# Main.net
KiCad netlist of a schematic drawn in EAGLE
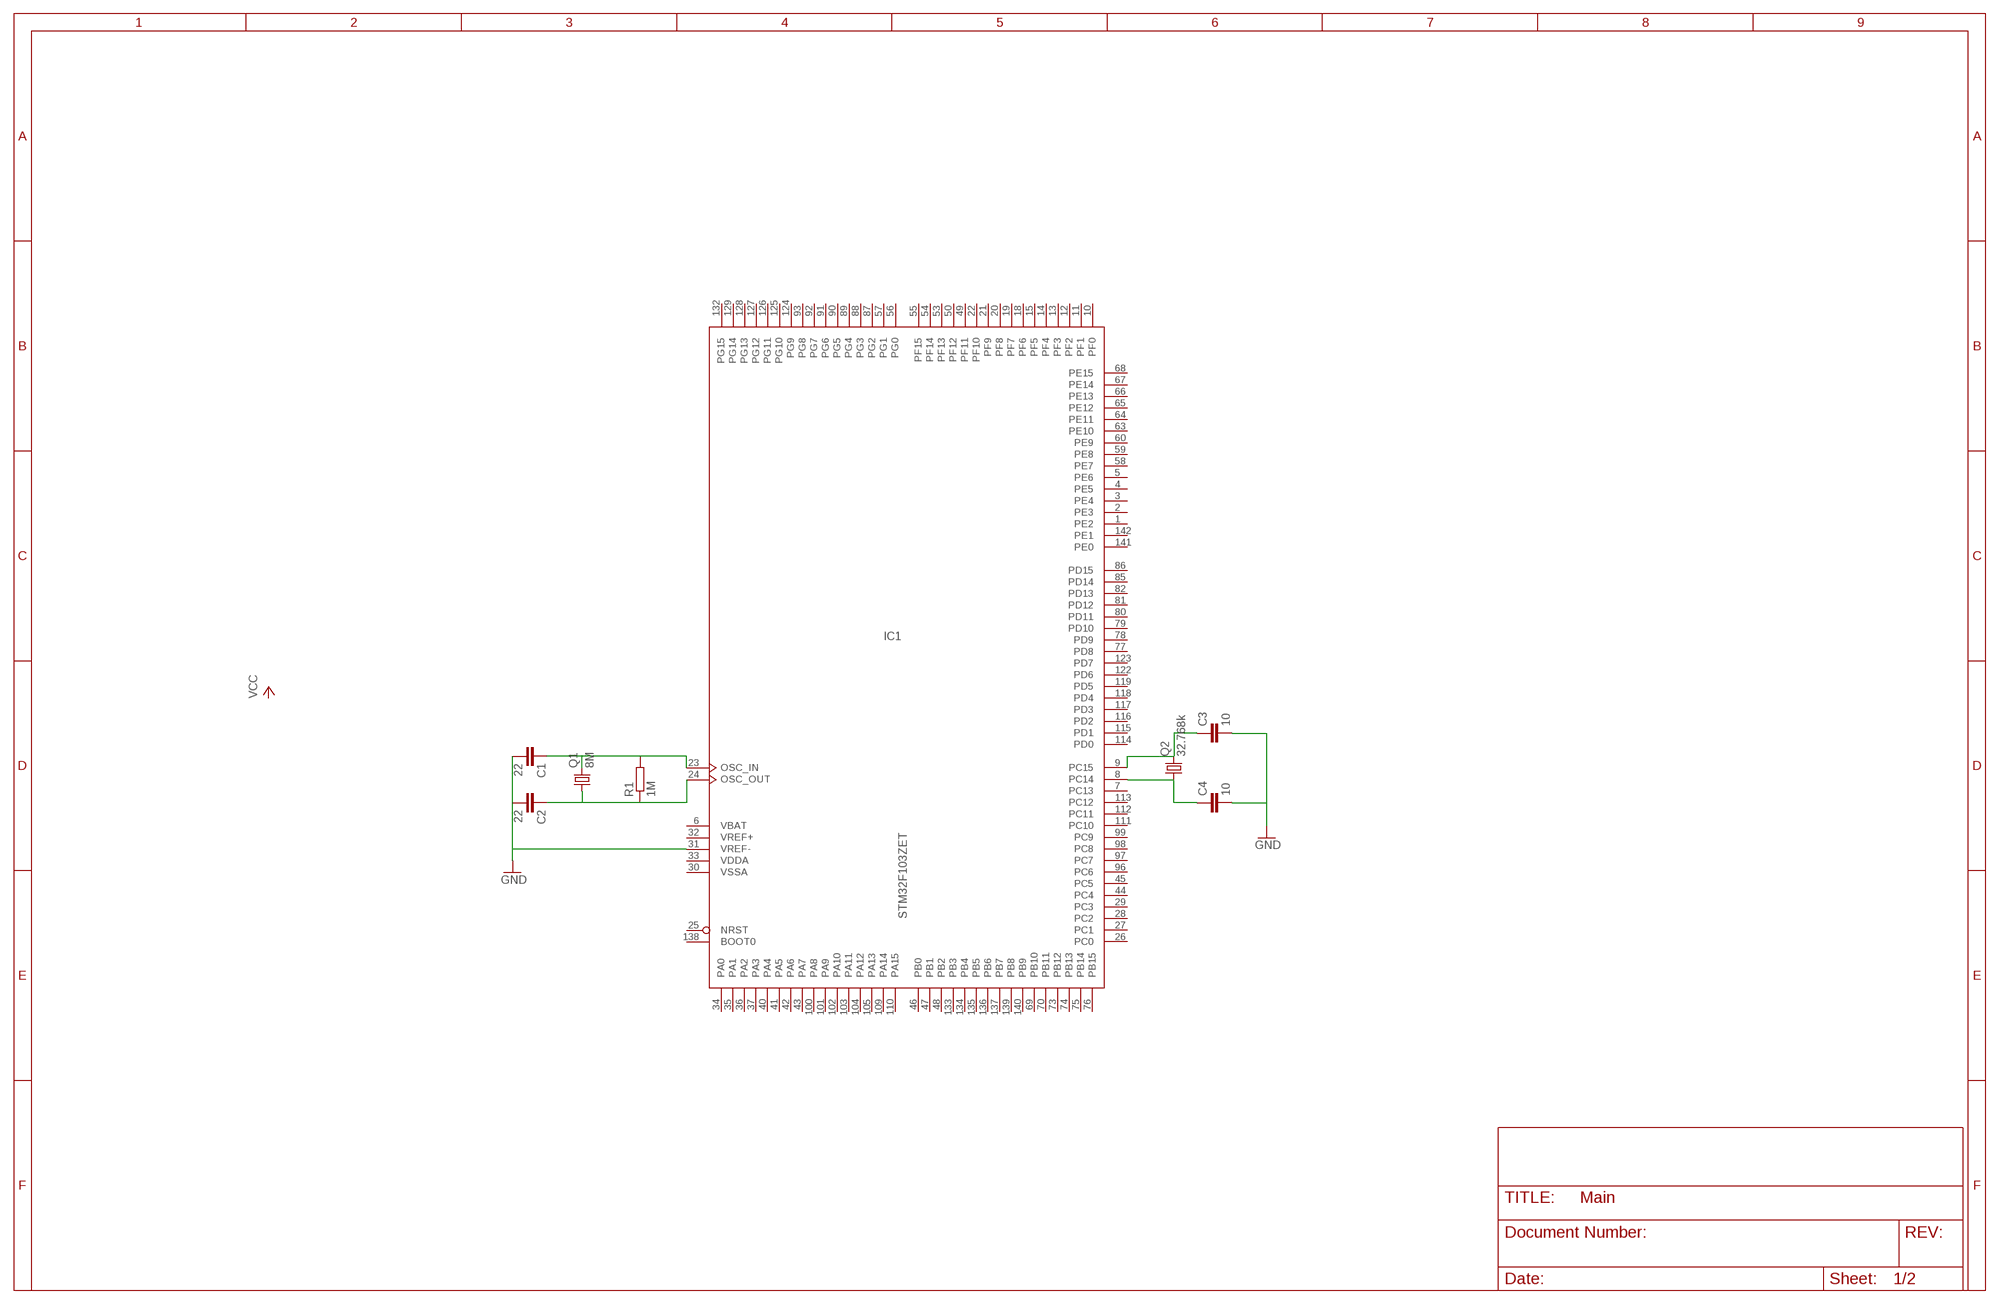
[diagram p0: schematic, sheet 1]
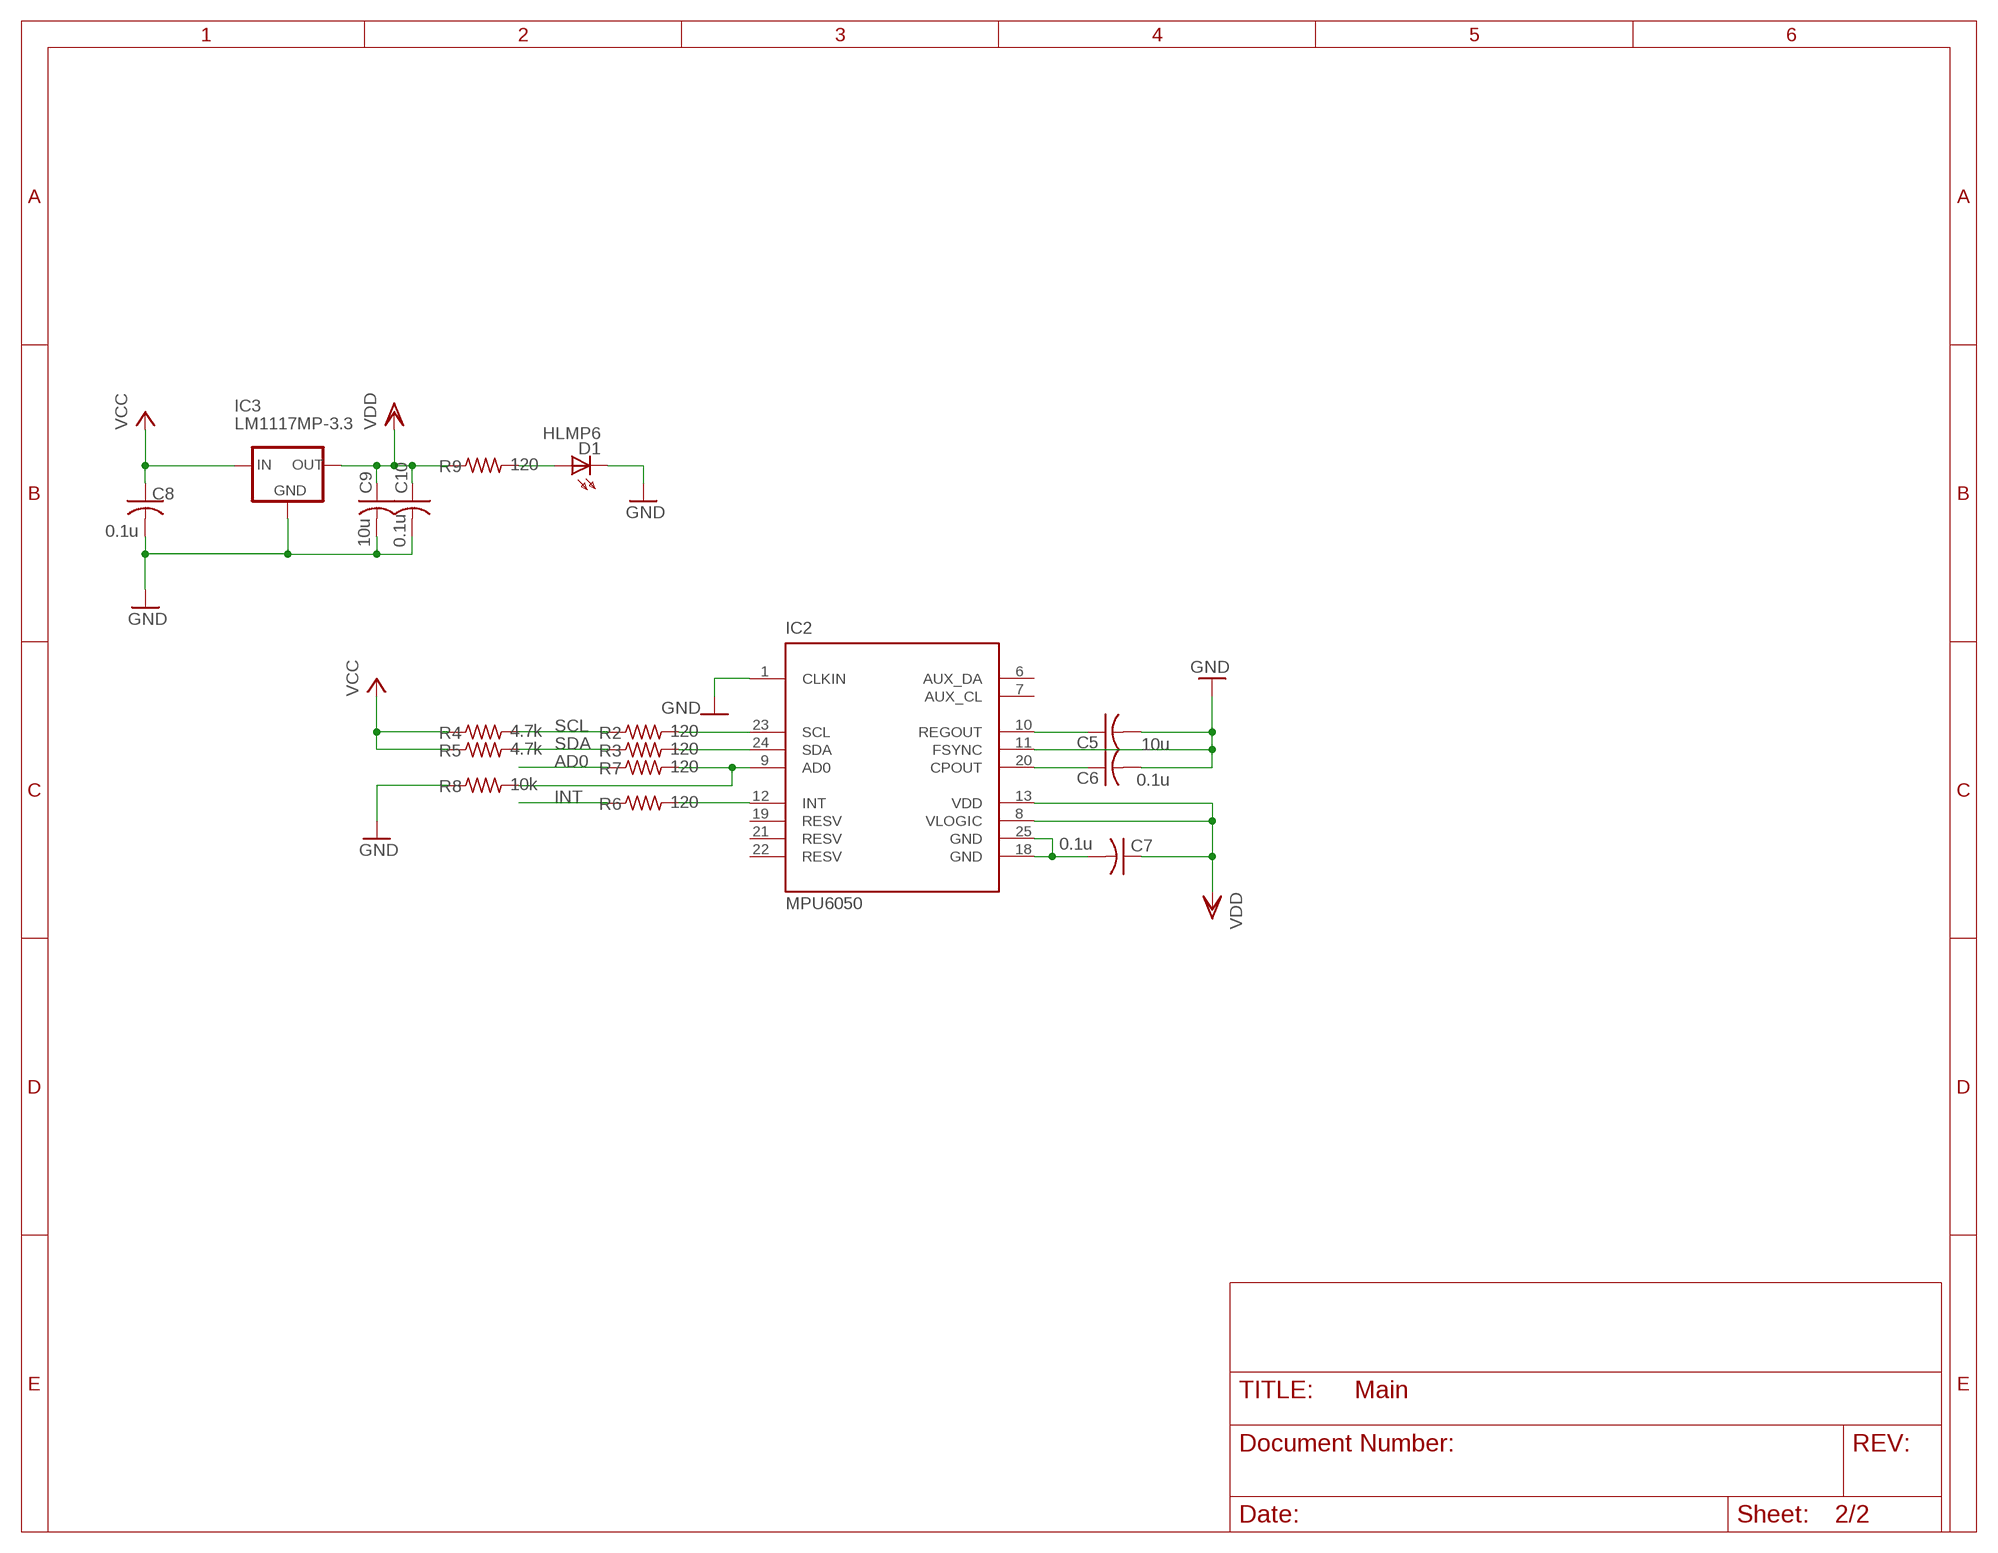
[diagram p1: schematic, sheet 2]

(export (version "E")
  (design (tool "Eeschema 10.0.6"))
  (components
    (comp (ref "C1")
      (value "22")
      (footprint "eagle-import:C0603")
      (libsource (lib "eagle-import") (part "C-EUC0603"))
    )
    (comp (ref "C2")
      (value "22")
      (footprint "eagle-import:C0603")
      (libsource (lib "eagle-import") (part "C-EUC0603"))
    )
    (comp (ref "C3")
      (value "10")
      (footprint "eagle-import:C0603")
      (libsource (lib "eagle-import") (part "C-EUC0603"))
    )
    (comp (ref "C4")
      (value "10")
      (footprint "eagle-import:C0603")
      (libsource (lib "eagle-import") (part "C-EUC0603"))
    )
    (comp (ref "IC1")
      (value "STM32F103ZET")
      (footprint "eagle-import:LQFP144")
      (libsource (lib "eagle-import") (part "STM32F103ZTE"))
    )
    (comp (ref "Q1")
      (value "8M")
      (footprint "eagle-import:HC49UP")
      (libsource (lib "eagle-import") (part "CRYSTALHC49UP"))
    )
    (comp (ref "Q2")
      (value "32.768k")
      (footprint "eagle-import:HC49UP")
      (libsource (lib "eagle-import") (part "CRYSTALHC49UP"))
    )
    (comp (ref "R1")
      (value "1M")
      (footprint "eagle-import:R0603")
      (libsource (lib "eagle-import") (part "R-EU_R0603"))
    )
    (comp (ref "C5")
      (value "10u")
      (footprint "eagle-import:C0603")
      (libsource (lib "eagle-import") (part "C-USC0603"))
    )
    (comp (ref "C6")
      (value "0.1u")
      (footprint "eagle-import:C0603")
      (libsource (lib "eagle-import") (part "C-USC0603"))
    )
    (comp (ref "C7")
      (value "0.1u")
      (footprint "eagle-import:C0603")
      (libsource (lib "eagle-import") (part "C-USC0603"))
    )
    (comp (ref "C8")
      (value "0.1u")
      (footprint "eagle-import:C0603")
      (libsource (lib "eagle-import") (part "C-USC0603"))
    )
    (comp (ref "C9")
      (value "10u")
      (footprint "eagle-import:C0603")
      (libsource (lib "eagle-import") (part "C-USC0603"))
    )
    (comp (ref "C10")
      (value "0.1u")
      (footprint "eagle-import:C0603")
      (libsource (lib "eagle-import") (part "C-USC0603"))
    )
    (comp (ref "D1")
      (value "HLMP6")
      (footprint "eagle-import:HLMP6")
      (fields (field (name "MF") "AGILENT TECHNOLOGIES") (field (name "MPN") "HLMP-6500"))
      (libsource (lib "eagle-import") (part "HLMP6"))
    )
    (comp (ref "IC2")
      (value "MPU6050")
      (footprint "eagle-import:QFN50P400X400X95-25T265X275N")
      (libsource (lib "eagle-import") (part "MPU6050"))
    )
    (comp (ref "IC3")
      (value "LM1117MP-3.3")
      (footprint "eagle-import:SOT223")
      (fields (field (name "MF") "Texas Instruments"))
      (libsource (lib "eagle-import") (part "LM1117?-MP3.3"))
    )
    (comp (ref "R2")
      (value "120")
      (footprint "eagle-import:R0603")
      (libsource (lib "eagle-import") (part "R-US_R0603"))
    )
    (comp (ref "R3")
      (value "120")
      (footprint "eagle-import:R0603")
      (libsource (lib "eagle-import") (part "R-US_R0603"))
    )
    (comp (ref "R4")
      (value "4.7k")
      (footprint "eagle-import:R0603")
      (libsource (lib "eagle-import") (part "R-US_R0603"))
    )
    (comp (ref "R5")
      (value "4.7k")
      (footprint "eagle-import:R0603")
      (libsource (lib "eagle-import") (part "R-US_R0603"))
    )
    (comp (ref "R6")
      (value "120")
      (footprint "eagle-import:R0603")
      (libsource (lib "eagle-import") (part "R-US_R0603"))
    )
    (comp (ref "R7")
      (value "120")
      (footprint "eagle-import:R0603")
      (libsource (lib "eagle-import") (part "R-US_R0603"))
    )
    (comp (ref "R8")
      (value "10k")
      (footprint "eagle-import:R0603")
      (libsource (lib "eagle-import") (part "R-US_R0603"))
    )
    (comp (ref "R9")
      (value "120")
      (footprint "eagle-import:R0603")
      (libsource (lib "eagle-import") (part "R-US_R0603"))
    )
  )
  (nets
    (net (code "1") (name "AD0") (class "Default")
      (node (ref "R7") (pin "1") (pinfunction "1_1") (pintype "passive"))
    )
    (net (code "2") (name "GND") (class "Default")
      (node (ref "C1") (pin "2") (pinfunction "2_2") (pintype "passive"))
      (node (ref "C10") (pin "2") (pinfunction "2_2") (pintype "passive"))
      (node (ref "C2") (pin "2") (pinfunction "2_2") (pintype "passive"))
      (node (ref "C3") (pin "2") (pinfunction "2_2") (pintype "passive"))
      (node (ref "C4") (pin "2") (pinfunction "2_2") (pintype "passive"))
      (node (ref "C5") (pin "2") (pinfunction "2_2") (pintype "passive"))
      (node (ref "C6") (pin "2") (pinfunction "2_2") (pintype "passive"))
      (node (ref "C8") (pin "2") (pinfunction "2_2") (pintype "passive"))
      (node (ref "C9") (pin "2") (pinfunction "2_2") (pintype "passive"))
      (node (ref "D1") (pin "K") (pinfunction "K_K") (pintype "passive"))
      (node (ref "IC1") (pin "31") (pinfunction "VREF-_31") (pintype "power_in"))
      (node (ref "IC2") (pin "1") (pinfunction "CLKIN_1") (pintype "input"))
      (node (ref "IC2") (pin "11") (pinfunction "FSYNC_11") (pintype "input"))
      (node (ref "IC3") (pin "1") (pinfunction "GND_1") (pintype "input"))
      (node (ref "R8") (pin "1") (pinfunction "1_1") (pintype "passive"))
    )
    (net (code "3") (name "INT") (class "Default")
      (node (ref "R6") (pin "1") (pinfunction "1_1") (pintype "passive"))
    )
    (net (code "4") (name "Net-(C7-Pad2)") (class "Default")
      (node (ref "C7") (pin "2") (pinfunction "2_2") (pintype "passive"))
      (node (ref "IC2") (pin "18") (pinfunction "GND_18") (pintype "power_in"))
      (node (ref "IC2") (pin "25") (pinfunction "GND_25") (pintype "power_in"))
    )
    (net (code "5") (name "Net-(D1-PadA)") (class "Default")
      (node (ref "D1") (pin "A") (pinfunction "A_A") (pintype "passive"))
      (node (ref "R9") (pin "2") (pinfunction "2_2") (pintype "passive"))
    )
    (net (code "6") (name "Net-(IC1A-OSC_IN)") (class "Default")
      (node (ref "C1") (pin "1") (pinfunction "1_1") (pintype "passive"))
      (node (ref "IC1") (pin "23") (pinfunction "OSC_IN_23") (pintype "bidirectional"))
      (node (ref "Q1") (pin "2") (pinfunction "2_2") (pintype "passive"))
      (node (ref "R1") (pin "2") (pinfunction "2_2") (pintype "passive"))
    )
    (net (code "7") (name "Net-(IC1A-OSC_OUT)") (class "Default")
      (node (ref "C2") (pin "1") (pinfunction "1_1") (pintype "passive"))
      (node (ref "IC1") (pin "24") (pinfunction "OSC_OUT_24") (pintype "bidirectional"))
      (node (ref "Q1") (pin "1") (pinfunction "1_1") (pintype "passive"))
      (node (ref "R1") (pin "1") (pinfunction "1_1") (pintype "passive"))
    )
    (net (code "8") (name "Net-(IC1A-PC14)") (class "Default")
      (node (ref "C4") (pin "1") (pinfunction "1_1") (pintype "passive"))
      (node (ref "IC1") (pin "8") (pinfunction "PC14_8") (pintype "bidirectional"))
      (node (ref "Q2") (pin "1") (pinfunction "1_1") (pintype "passive"))
    )
    (net (code "9") (name "Net-(IC1A-PC15)") (class "Default")
      (node (ref "C3") (pin "1") (pinfunction "1_1") (pintype "passive"))
      (node (ref "IC1") (pin "9") (pinfunction "PC15_9") (pintype "bidirectional"))
      (node (ref "Q2") (pin "2") (pinfunction "2_2") (pintype "passive"))
    )
    (net (code "10") (name "Net-(IC2A-AD0)") (class "Default")
      (node (ref "IC2") (pin "9") (pinfunction "AD0_9") (pintype "input"))
      (node (ref "R7") (pin "2") (pinfunction "2_2") (pintype "passive"))
      (node (ref "R8") (pin "2") (pinfunction "2_2") (pintype "passive"))
    )
    (net (code "11") (name "Net-(IC2A-CPOUT)") (class "Default")
      (node (ref "C6") (pin "1") (pinfunction "1_1") (pintype "passive"))
      (node (ref "IC2") (pin "20") (pinfunction "CPOUT_20") (pintype "output"))
    )
    (net (code "12") (name "Net-(IC2A-INT)") (class "Default")
      (node (ref "IC2") (pin "12") (pinfunction "INT_12") (pintype "open_collector"))
      (node (ref "R6") (pin "2") (pinfunction "2_2") (pintype "passive"))
    )
    (net (code "13") (name "Net-(IC2A-REGOUT)") (class "Default")
      (node (ref "C5") (pin "1") (pinfunction "1_1") (pintype "passive"))
      (node (ref "IC2") (pin "10") (pinfunction "REGOUT_10") (pintype "output"))
    )
    (net (code "14") (name "Net-(IC2A-SCL)") (class "Default")
      (node (ref "IC2") (pin "23") (pinfunction "SCL_23") (pintype "input"))
      (node (ref "R2") (pin "2") (pinfunction "2_2") (pintype "passive"))
    )
    (net (code "15") (name "Net-(IC2A-SDA)") (class "Default")
      (node (ref "IC2") (pin "24") (pinfunction "SDA_24") (pintype "bidirectional"))
      (node (ref "R3") (pin "2") (pinfunction "2_2") (pintype "passive"))
    )
    (net (code "16") (name "SCL") (class "Default")
      (node (ref "R2") (pin "1") (pinfunction "1_1") (pintype "passive"))
      (node (ref "R4") (pin "2") (pinfunction "2_2") (pintype "passive"))
    )
    (net (code "17") (name "SDA") (class "Default")
      (node (ref "R3") (pin "1") (pinfunction "1_1") (pintype "passive"))
      (node (ref "R5") (pin "2") (pinfunction "2_2") (pintype "passive"))
    )
    (net (code "18") (name "VBAT") (class "Default")
      (node (ref "IC1") (pin "6") (pinfunction "VBAT_6") (pintype "power_in"))
    )
    (net (code "19") (name "VCC") (class "Default")
      (node (ref "C8") (pin "1") (pinfunction "1_1") (pintype "passive"))
      (node (ref "IC3") (pin "3") (pinfunction "IN_3") (pintype "input"))
      (node (ref "R4") (pin "1") (pinfunction "1_1") (pintype "passive"))
      (node (ref "R5") (pin "1") (pinfunction "1_1") (pintype "passive"))
    )
    (net (code "20") (name "VDD") (class "Default")
      (node (ref "C10") (pin "1") (pinfunction "1_1") (pintype "passive"))
      (node (ref "C7") (pin "1") (pinfunction "1_1") (pintype "passive"))
      (node (ref "C9") (pin "1") (pinfunction "1_1") (pintype "passive"))
      (node (ref "IC2") (pin "13") (pinfunction "VDD_13") (pintype "power_in"))
      (node (ref "IC2") (pin "8") (pinfunction "VLOGIC_8") (pintype "power_in"))
      (node (ref "IC3") (pin "2") (pinfunction "OUT_2") (pintype "passive"))
      (node (ref "IC3") (pin "4") (pinfunction "OUT_4") (pintype "passive"))
      (node (ref "R9") (pin "1") (pinfunction "1_1") (pintype "passive"))
    )
    (net (code "21") (name "VDDA") (class "Default")
      (node (ref "IC1") (pin "33") (pinfunction "VDDA_33") (pintype "power_in"))
    )
    (net (code "22") (name "VREF+") (class "Default")
      (node (ref "IC1") (pin "32") (pinfunction "VREF+_32") (pintype "power_in"))
    )
    (net (code "23") (name "VSSA") (class "Default")
      (node (ref "IC1") (pin "30") (pinfunction "VSSA_30") (pintype "power_in"))
    )
    (net (code "24") (name "unconnected-(IC1A-BOOT0-Pad138)") (class "Default")
      (node (ref "IC1") (pin "138") (pinfunction "BOOT0_138") (pintype "input"))
    )
    (net (code "25") (name "unconnected-(IC1A-NRST-Pad25)") (class "Default")
      (node (ref "IC1") (pin "25") (pinfunction "NRST_25") (pintype "bidirectional"))
    )
    (net (code "26") (name "unconnected-(IC1A-PA0-Pad34)") (class "Default")
      (node (ref "IC1") (pin "34") (pinfunction "PA0_34") (pintype "bidirectional"))
    )
    (net (code "27") (name "unconnected-(IC1A-PA1-Pad35)") (class "Default")
      (node (ref "IC1") (pin "35") (pinfunction "PA1_35") (pintype "bidirectional"))
    )
    (net (code "28") (name "unconnected-(IC1A-PA2-Pad36)") (class "Default")
      (node (ref "IC1") (pin "36") (pinfunction "PA2_36") (pintype "bidirectional"))
    )
    (net (code "29") (name "unconnected-(IC1A-PA3-Pad37)") (class "Default")
      (node (ref "IC1") (pin "37") (pinfunction "PA3_37") (pintype "bidirectional"))
    )
    (net (code "30") (name "unconnected-(IC1A-PA4-Pad40)") (class "Default")
      (node (ref "IC1") (pin "40") (pinfunction "PA4_40") (pintype "bidirectional"))
    )
    (net (code "31") (name "unconnected-(IC1A-PA5-Pad41)") (class "Default")
      (node (ref "IC1") (pin "41") (pinfunction "PA5_41") (pintype "bidirectional"))
    )
    (net (code "32") (name "unconnected-(IC1A-PA6-Pad42)") (class "Default")
      (node (ref "IC1") (pin "42") (pinfunction "PA6_42") (pintype "bidirectional"))
    )
    (net (code "33") (name "unconnected-(IC1A-PA7-Pad43)") (class "Default")
      (node (ref "IC1") (pin "43") (pinfunction "PA7_43") (pintype "bidirectional"))
    )
    (net (code "34") (name "unconnected-(IC1A-PA8-Pad100)") (class "Default")
      (node (ref "IC1") (pin "100") (pinfunction "PA8_100") (pintype "bidirectional"))
    )
    (net (code "35") (name "unconnected-(IC1A-PA9-Pad101)") (class "Default")
      (node (ref "IC1") (pin "101") (pinfunction "PA9_101") (pintype "bidirectional"))
    )
    (net (code "36") (name "unconnected-(IC1A-PA10-Pad102)") (class "Default")
      (node (ref "IC1") (pin "102") (pinfunction "PA10_102") (pintype "bidirectional"))
    )
    (net (code "37") (name "unconnected-(IC1A-PA11-Pad103)") (class "Default")
      (node (ref "IC1") (pin "103") (pinfunction "PA11_103") (pintype "bidirectional"))
    )
    (net (code "38") (name "unconnected-(IC1A-PA12-Pad104)") (class "Default")
      (node (ref "IC1") (pin "104") (pinfunction "PA12_104") (pintype "bidirectional"))
    )
    (net (code "39") (name "unconnected-(IC1A-PA13-Pad105)") (class "Default")
      (node (ref "IC1") (pin "105") (pinfunction "PA13_105") (pintype "bidirectional"))
    )
    (net (code "40") (name "unconnected-(IC1A-PA14-Pad109)") (class "Default")
      (node (ref "IC1") (pin "109") (pinfunction "PA14_109") (pintype "bidirectional"))
    )
    (net (code "41") (name "unconnected-(IC1A-PA15-Pad110)") (class "Default")
      (node (ref "IC1") (pin "110") (pinfunction "PA15_110") (pintype "bidirectional"))
    )
    (net (code "42") (name "unconnected-(IC1A-PB0-Pad46)") (class "Default")
      (node (ref "IC1") (pin "46") (pinfunction "PB0_46") (pintype "bidirectional"))
    )
    (net (code "43") (name "unconnected-(IC1A-PB1-Pad47)") (class "Default")
      (node (ref "IC1") (pin "47") (pinfunction "PB1_47") (pintype "bidirectional"))
    )
    (net (code "44") (name "unconnected-(IC1A-PB2-Pad48)") (class "Default")
      (node (ref "IC1") (pin "48") (pinfunction "PB2_48") (pintype "bidirectional"))
    )
    (net (code "45") (name "unconnected-(IC1A-PB3-Pad133)") (class "Default")
      (node (ref "IC1") (pin "133") (pinfunction "PB3_133") (pintype "bidirectional"))
    )
    (net (code "46") (name "unconnected-(IC1A-PB4-Pad134)") (class "Default")
      (node (ref "IC1") (pin "134") (pinfunction "PB4_134") (pintype "bidirectional"))
    )
    (net (code "47") (name "unconnected-(IC1A-PB5-Pad135)") (class "Default")
      (node (ref "IC1") (pin "135") (pinfunction "PB5_135") (pintype "bidirectional"))
    )
    (net (code "48") (name "unconnected-(IC1A-PB6-Pad136)") (class "Default")
      (node (ref "IC1") (pin "136") (pinfunction "PB6_136") (pintype "bidirectional"))
    )
    (net (code "49") (name "unconnected-(IC1A-PB7-Pad137)") (class "Default")
      (node (ref "IC1") (pin "137") (pinfunction "PB7_137") (pintype "bidirectional"))
    )
    (net (code "50") (name "unconnected-(IC1A-PB8-Pad139)") (class "Default")
      (node (ref "IC1") (pin "139") (pinfunction "PB8_139") (pintype "bidirectional"))
    )
    (net (code "51") (name "unconnected-(IC1A-PB9-Pad140)") (class "Default")
      (node (ref "IC1") (pin "140") (pinfunction "PB9_140") (pintype "bidirectional"))
    )
    (net (code "52") (name "unconnected-(IC1A-PB10-Pad69)") (class "Default")
      (node (ref "IC1") (pin "69") (pinfunction "PB10_69") (pintype "bidirectional"))
    )
    (net (code "53") (name "unconnected-(IC1A-PB11-Pad70)") (class "Default")
      (node (ref "IC1") (pin "70") (pinfunction "PB11_70") (pintype "bidirectional"))
    )
    (net (code "54") (name "unconnected-(IC1A-PB12-Pad73)") (class "Default")
      (node (ref "IC1") (pin "73") (pinfunction "PB12_73") (pintype "bidirectional"))
    )
    (net (code "55") (name "unconnected-(IC1A-PB13-Pad74)") (class "Default")
      (node (ref "IC1") (pin "74") (pinfunction "PB13_74") (pintype "bidirectional"))
    )
    (net (code "56") (name "unconnected-(IC1A-PB14-Pad75)") (class "Default")
      (node (ref "IC1") (pin "75") (pinfunction "PB14_75") (pintype "bidirectional"))
    )
    (net (code "57") (name "unconnected-(IC1A-PB15-Pad76)") (class "Default")
      (node (ref "IC1") (pin "76") (pinfunction "PB15_76") (pintype "bidirectional"))
    )
    (net (code "58") (name "unconnected-(IC1A-PC0-Pad26)") (class "Default")
      (node (ref "IC1") (pin "26") (pinfunction "PC0_26") (pintype "bidirectional"))
    )
    (net (code "59") (name "unconnected-(IC1A-PC1-Pad27)") (class "Default")
      (node (ref "IC1") (pin "27") (pinfunction "PC1_27") (pintype "bidirectional"))
    )
    (net (code "60") (name "unconnected-(IC1A-PC2-Pad28)") (class "Default")
      (node (ref "IC1") (pin "28") (pinfunction "PC2_28") (pintype "bidirectional"))
    )
    (net (code "61") (name "unconnected-(IC1A-PC3-Pad29)") (class "Default")
      (node (ref "IC1") (pin "29") (pinfunction "PC3_29") (pintype "bidirectional"))
    )
    (net (code "62") (name "unconnected-(IC1A-PC4-Pad44)") (class "Default")
      (node (ref "IC1") (pin "44") (pinfunction "PC4_44") (pintype "bidirectional"))
    )
    (net (code "63") (name "unconnected-(IC1A-PC5-Pad45)") (class "Default")
      (node (ref "IC1") (pin "45") (pinfunction "PC5_45") (pintype "bidirectional"))
    )
    (net (code "64") (name "unconnected-(IC1A-PC6-Pad96)") (class "Default")
      (node (ref "IC1") (pin "96") (pinfunction "PC6_96") (pintype "bidirectional"))
    )
    (net (code "65") (name "unconnected-(IC1A-PC7-Pad97)") (class "Default")
      (node (ref "IC1") (pin "97") (pinfunction "PC7_97") (pintype "bidirectional"))
    )
    (net (code "66") (name "unconnected-(IC1A-PC8-Pad98)") (class "Default")
      (node (ref "IC1") (pin "98") (pinfunction "PC8_98") (pintype "bidirectional"))
    )
    (net (code "67") (name "unconnected-(IC1A-PC9-Pad99)") (class "Default")
      (node (ref "IC1") (pin "99") (pinfunction "PC9_99") (pintype "bidirectional"))
    )
    (net (code "68") (name "unconnected-(IC1A-PC10-Pad111)") (class "Default")
      (node (ref "IC1") (pin "111") (pinfunction "PC10_111") (pintype "bidirectional"))
    )
    (net (code "69") (name "unconnected-(IC1A-PC11-Pad112)") (class "Default")
      (node (ref "IC1") (pin "112") (pinfunction "PC11_112") (pintype "bidirectional"))
    )
    (net (code "70") (name "unconnected-(IC1A-PC12-Pad113)") (class "Default")
      (node (ref "IC1") (pin "113") (pinfunction "PC12_113") (pintype "bidirectional"))
    )
    (net (code "71") (name "unconnected-(IC1A-PC13-Pad7)") (class "Default")
      (node (ref "IC1") (pin "7") (pinfunction "PC13_7") (pintype "bidirectional"))
    )
    (net (code "72") (name "unconnected-(IC1A-PD0-Pad114)") (class "Default")
      (node (ref "IC1") (pin "114") (pinfunction "PD0_114") (pintype "bidirectional"))
    )
    (net (code "73") (name "unconnected-(IC1A-PD1-Pad115)") (class "Default")
      (node (ref "IC1") (pin "115") (pinfunction "PD1_115") (pintype "bidirectional"))
    )
    (net (code "74") (name "unconnected-(IC1A-PD2-Pad116)") (class "Default")
      (node (ref "IC1") (pin "116") (pinfunction "PD2_116") (pintype "bidirectional"))
    )
    (net (code "75") (name "unconnected-(IC1A-PD3-Pad117)") (class "Default")
      (node (ref "IC1") (pin "117") (pinfunction "PD3_117") (pintype "bidirectional"))
    )
    (net (code "76") (name "unconnected-(IC1A-PD4-Pad118)") (class "Default")
      (node (ref "IC1") (pin "118") (pinfunction "PD4_118") (pintype "bidirectional"))
    )
    (net (code "77") (name "unconnected-(IC1A-PD5-Pad119)") (class "Default")
      (node (ref "IC1") (pin "119") (pinfunction "PD5_119") (pintype "bidirectional"))
    )
    (net (code "78") (name "unconnected-(IC1A-PD6-Pad122)") (class "Default")
      (node (ref "IC1") (pin "122") (pinfunction "PD6_122") (pintype "bidirectional"))
    )
    (net (code "79") (name "unconnected-(IC1A-PD7-Pad123)") (class "Default")
      (node (ref "IC1") (pin "123") (pinfunction "PD7_123") (pintype "bidirectional"))
    )
    (net (code "80") (name "unconnected-(IC1A-PD8-Pad77)") (class "Default")
      (node (ref "IC1") (pin "77") (pinfunction "PD8_77") (pintype "bidirectional"))
    )
    (net (code "81") (name "unconnected-(IC1A-PD9-Pad78)") (class "Default")
      (node (ref "IC1") (pin "78") (pinfunction "PD9_78") (pintype "bidirectional"))
    )
    (net (code "82") (name "unconnected-(IC1A-PD10-Pad79)") (class "Default")
      (node (ref "IC1") (pin "79") (pinfunction "PD10_79") (pintype "bidirectional"))
    )
    (net (code "83") (name "unconnected-(IC1A-PD11-Pad80)") (class "Default")
      (node (ref "IC1") (pin "80") (pinfunction "PD11_80") (pintype "bidirectional"))
    )
    (net (code "84") (name "unconnected-(IC1A-PD12-Pad81)") (class "Default")
      (node (ref "IC1") (pin "81") (pinfunction "PD12_81") (pintype "bidirectional"))
    )
    (net (code "85") (name "unconnected-(IC1A-PD13-Pad82)") (class "Default")
      (node (ref "IC1") (pin "82") (pinfunction "PD13_82") (pintype "bidirectional"))
    )
    (net (code "86") (name "unconnected-(IC1A-PD14-Pad85)") (class "Default")
      (node (ref "IC1") (pin "85") (pinfunction "PD14_85") (pintype "bidirectional"))
    )
    (net (code "87") (name "unconnected-(IC1A-PD15-Pad86)") (class "Default")
      (node (ref "IC1") (pin "86") (pinfunction "PD15_86") (pintype "bidirectional"))
    )
    (net (code "88") (name "unconnected-(IC1A-PE0-Pad141)") (class "Default")
      (node (ref "IC1") (pin "141") (pinfunction "PE0_141") (pintype "bidirectional"))
    )
    (net (code "89") (name "unconnected-(IC1A-PE1-Pad142)") (class "Default")
      (node (ref "IC1") (pin "142") (pinfunction "PE1_142") (pintype "bidirectional"))
    )
    (net (code "90") (name "unconnected-(IC1A-PE2-Pad1)") (class "Default")
      (node (ref "IC1") (pin "1") (pinfunction "PE2_1") (pintype "bidirectional"))
    )
    (net (code "91") (name "unconnected-(IC1A-PE3-Pad2)") (class "Default")
      (node (ref "IC1") (pin "2") (pinfunction "PE3_2") (pintype "bidirectional"))
    )
    (net (code "92") (name "unconnected-(IC1A-PE4-Pad3)") (class "Default")
      (node (ref "IC1") (pin "3") (pinfunction "PE4_3") (pintype "bidirectional"))
    )
    (net (code "93") (name "unconnected-(IC1A-PE5-Pad4)") (class "Default")
      (node (ref "IC1") (pin "4") (pinfunction "PE5_4") (pintype "bidirectional"))
    )
    (net (code "94") (name "unconnected-(IC1A-PE6-Pad5)") (class "Default")
      (node (ref "IC1") (pin "5") (pinfunction "PE6_5") (pintype "bidirectional"))
    )
    (net (code "95") (name "unconnected-(IC1A-PE7-Pad58)") (class "Default")
      (node (ref "IC1") (pin "58") (pinfunction "PE7_58") (pintype "bidirectional"))
    )
    (net (code "96") (name "unconnected-(IC1A-PE8-Pad59)") (class "Default")
      (node (ref "IC1") (pin "59") (pinfunction "PE8_59") (pintype "bidirectional"))
    )
    (net (code "97") (name "unconnected-(IC1A-PE9-Pad60)") (class "Default")
      (node (ref "IC1") (pin "60") (pinfunction "PE9_60") (pintype "bidirectional"))
    )
    (net (code "98") (name "unconnected-(IC1A-PE10-Pad63)") (class "Default")
      (node (ref "IC1") (pin "63") (pinfunction "PE10_63") (pintype "bidirectional"))
    )
    (net (code "99") (name "unconnected-(IC1A-PE11-Pad64)") (class "Default")
      (node (ref "IC1") (pin "64") (pinfunction "PE11_64") (pintype "bidirectional"))
    )
    (net (code "100") (name "unconnected-(IC1A-PE12-Pad65)") (class "Default")
      (node (ref "IC1") (pin "65") (pinfunction "PE12_65") (pintype "bidirectional"))
    )
    (net (code "101") (name "unconnected-(IC1A-PE13-Pad66)") (class "Default")
      (node (ref "IC1") (pin "66") (pinfunction "PE13_66") (pintype "bidirectional"))
    )
    (net (code "102") (name "unconnected-(IC1A-PE14-Pad67)") (class "Default")
      (node (ref "IC1") (pin "67") (pinfunction "PE14_67") (pintype "bidirectional"))
    )
    (net (code "103") (name "unconnected-(IC1A-PE15-Pad68)") (class "Default")
      (node (ref "IC1") (pin "68") (pinfunction "PE15_68") (pintype "bidirectional"))
    )
    (net (code "104") (name "unconnected-(IC1A-PF0-Pad10)") (class "Default")
      (node (ref "IC1") (pin "10") (pinfunction "PF0_10") (pintype "bidirectional"))
    )
    (net (code "105") (name "unconnected-(IC1A-PF1-Pad11)") (class "Default")
      (node (ref "IC1") (pin "11") (pinfunction "PF1_11") (pintype "bidirectional"))
    )
    (net (code "106") (name "unconnected-(IC1A-PF2-Pad12)") (class "Default")
      (node (ref "IC1") (pin "12") (pinfunction "PF2_12") (pintype "bidirectional"))
    )
    (net (code "107") (name "unconnected-(IC1A-PF3-Pad13)") (class "Default")
      (node (ref "IC1") (pin "13") (pinfunction "PF3_13") (pintype "bidirectional"))
    )
    (net (code "108") (name "unconnected-(IC1A-PF4-Pad14)") (class "Default")
      (node (ref "IC1") (pin "14") (pinfunction "PF4_14") (pintype "bidirectional"))
    )
    (net (code "109") (name "unconnected-(IC1A-PF5-Pad15)") (class "Default")
      (node (ref "IC1") (pin "15") (pinfunction "PF5_15") (pintype "bidirectional"))
    )
    (net (code "110") (name "unconnected-(IC1A-PF6-Pad18)") (class "Default")
      (node (ref "IC1") (pin "18") (pinfunction "PF6_18") (pintype "bidirectional"))
    )
    (net (code "111") (name "unconnected-(IC1A-PF7-Pad19)") (class "Default")
      (node (ref "IC1") (pin "19") (pinfunction "PF7_19") (pintype "bidirectional"))
    )
    (net (code "112") (name "unconnected-(IC1A-PF8-Pad20)") (class "Default")
      (node (ref "IC1") (pin "20") (pinfunction "PF8_20") (pintype "bidirectional"))
    )
    (net (code "113") (name "unconnected-(IC1A-PF9-Pad21)") (class "Default")
      (node (ref "IC1") (pin "21") (pinfunction "PF9_21") (pintype "bidirectional"))
    )
    (net (code "114") (name "unconnected-(IC1A-PF10-Pad22)") (class "Default")
      (node (ref "IC1") (pin "22") (pinfunction "PF10_22") (pintype "bidirectional"))
    )
    (net (code "115") (name "unconnected-(IC1A-PF11-Pad49)") (class "Default")
      (node (ref "IC1") (pin "49") (pinfunction "PF11_49") (pintype "bidirectional"))
    )
    (net (code "116") (name "unconnected-(IC1A-PF12-Pad50)") (class "Default")
      (node (ref "IC1") (pin "50") (pinfunction "PF12_50") (pintype "bidirectional"))
    )
    (net (code "117") (name "unconnected-(IC1A-PF13-Pad53)") (class "Default")
      (node (ref "IC1") (pin "53") (pinfunction "PF13_53") (pintype "bidirectional"))
    )
    (net (code "118") (name "unconnected-(IC1A-PF14-Pad54)") (class "Default")
      (node (ref "IC1") (pin "54") (pinfunction "PF14_54") (pintype "bidirectional"))
    )
    (net (code "119") (name "unconnected-(IC1A-PF15-Pad55)") (class "Default")
      (node (ref "IC1") (pin "55") (pinfunction "PF15_55") (pintype "bidirectional"))
    )
    (net (code "120") (name "unconnected-(IC1A-PG0-Pad56)") (class "Default")
      (node (ref "IC1") (pin "56") (pinfunction "PG0_56") (pintype "bidirectional"))
    )
    (net (code "121") (name "unconnected-(IC1A-PG1-Pad57)") (class "Default")
      (node (ref "IC1") (pin "57") (pinfunction "PG1_57") (pintype "bidirectional"))
    )
    (net (code "122") (name "unconnected-(IC1A-PG2-Pad87)") (class "Default")
      (node (ref "IC1") (pin "87") (pinfunction "PG2_87") (pintype "bidirectional"))
    )
    (net (code "123") (name "unconnected-(IC1A-PG3-Pad88)") (class "Default")
      (node (ref "IC1") (pin "88") (pinfunction "PG3_88") (pintype "bidirectional"))
    )
    (net (code "124") (name "unconnected-(IC1A-PG4-Pad89)") (class "Default")
      (node (ref "IC1") (pin "89") (pinfunction "PG4_89") (pintype "bidirectional"))
    )
    (net (code "125") (name "unconnected-(IC1A-PG5-Pad90)") (class "Default")
      (node (ref "IC1") (pin "90") (pinfunction "PG5_90") (pintype "bidirectional"))
    )
    (net (code "126") (name "unconnected-(IC1A-PG6-Pad91)") (class "Default")
      (node (ref "IC1") (pin "91") (pinfunction "PG6_91") (pintype "bidirectional"))
    )
    (net (code "127") (name "unconnected-(IC1A-PG7-Pad92)") (class "Default")
      (node (ref "IC1") (pin "92") (pinfunction "PG7_92") (pintype "bidirectional"))
    )
    (net (code "128") (name "unconnected-(IC1A-PG8-Pad93)") (class "Default")
      (node (ref "IC1") (pin "93") (pinfunction "PG8_93") (pintype "bidirectional"))
    )
    (net (code "129") (name "unconnected-(IC1A-PG9-Pad124)") (class "Default")
      (node (ref "IC1") (pin "124") (pinfunction "PG9_124") (pintype "bidirectional"))
    )
    (net (code "130") (name "unconnected-(IC1A-PG10-Pad125)") (class "Default")
      (node (ref "IC1") (pin "125") (pinfunction "PG10_125") (pintype "bidirectional"))
    )
    (net (code "131") (name "unconnected-(IC1A-PG11-Pad126)") (class "Default")
      (node (ref "IC1") (pin "126") (pinfunction "PG11_126") (pintype "bidirectional"))
    )
    (net (code "132") (name "unconnected-(IC1A-PG12-Pad127)") (class "Default")
      (node (ref "IC1") (pin "127") (pinfunction "PG12_127") (pintype "bidirectional"))
    )
    (net (code "133") (name "unconnected-(IC1A-PG13-Pad128)") (class "Default")
      (node (ref "IC1") (pin "128") (pinfunction "PG13_128") (pintype "bidirectional"))
    )
    (net (code "134") (name "unconnected-(IC1A-PG14-Pad129)") (class "Default")
      (node (ref "IC1") (pin "129") (pinfunction "PG14_129") (pintype "bidirectional"))
    )
    (net (code "135") (name "unconnected-(IC1A-PG15-Pad132)") (class "Default")
      (node (ref "IC1") (pin "132") (pinfunction "PG15_132") (pintype "bidirectional"))
    )
    (net (code "136") (name "unconnected-(IC2A-AUX_CL-Pad7)") (class "Default")
      (node (ref "IC2") (pin "7") (pinfunction "AUX_CL_7") (pintype "bidirectional"))
    )
    (net (code "137") (name "unconnected-(IC2A-AUX_DA-Pad6)") (class "Default")
      (node (ref "IC2") (pin "6") (pinfunction "AUX_DA_6") (pintype "bidirectional"))
    )
    (net (code "138") (name "unconnected-(IC2A-RESV-Pad19)") (class "Default")
      (node (ref "IC2") (pin "19") (pinfunction "RESV_19") (pintype "passive"))
    )
    (net (code "139") (name "unconnected-(IC2A-RESV-Pad21)") (class "Default")
      (node (ref "IC2") (pin "21") (pinfunction "RESV_21") (pintype "passive"))
    )
    (net (code "140") (name "unconnected-(IC2A-RESV-Pad22)") (class "Default")
      (node (ref "IC2") (pin "22") (pinfunction "RESV_22") (pintype "passive"))
    )
  )
)
